# 7segement4digits1badidea-feathershield-m.net
KiCad netlist of a schematic drawn in EAGLE
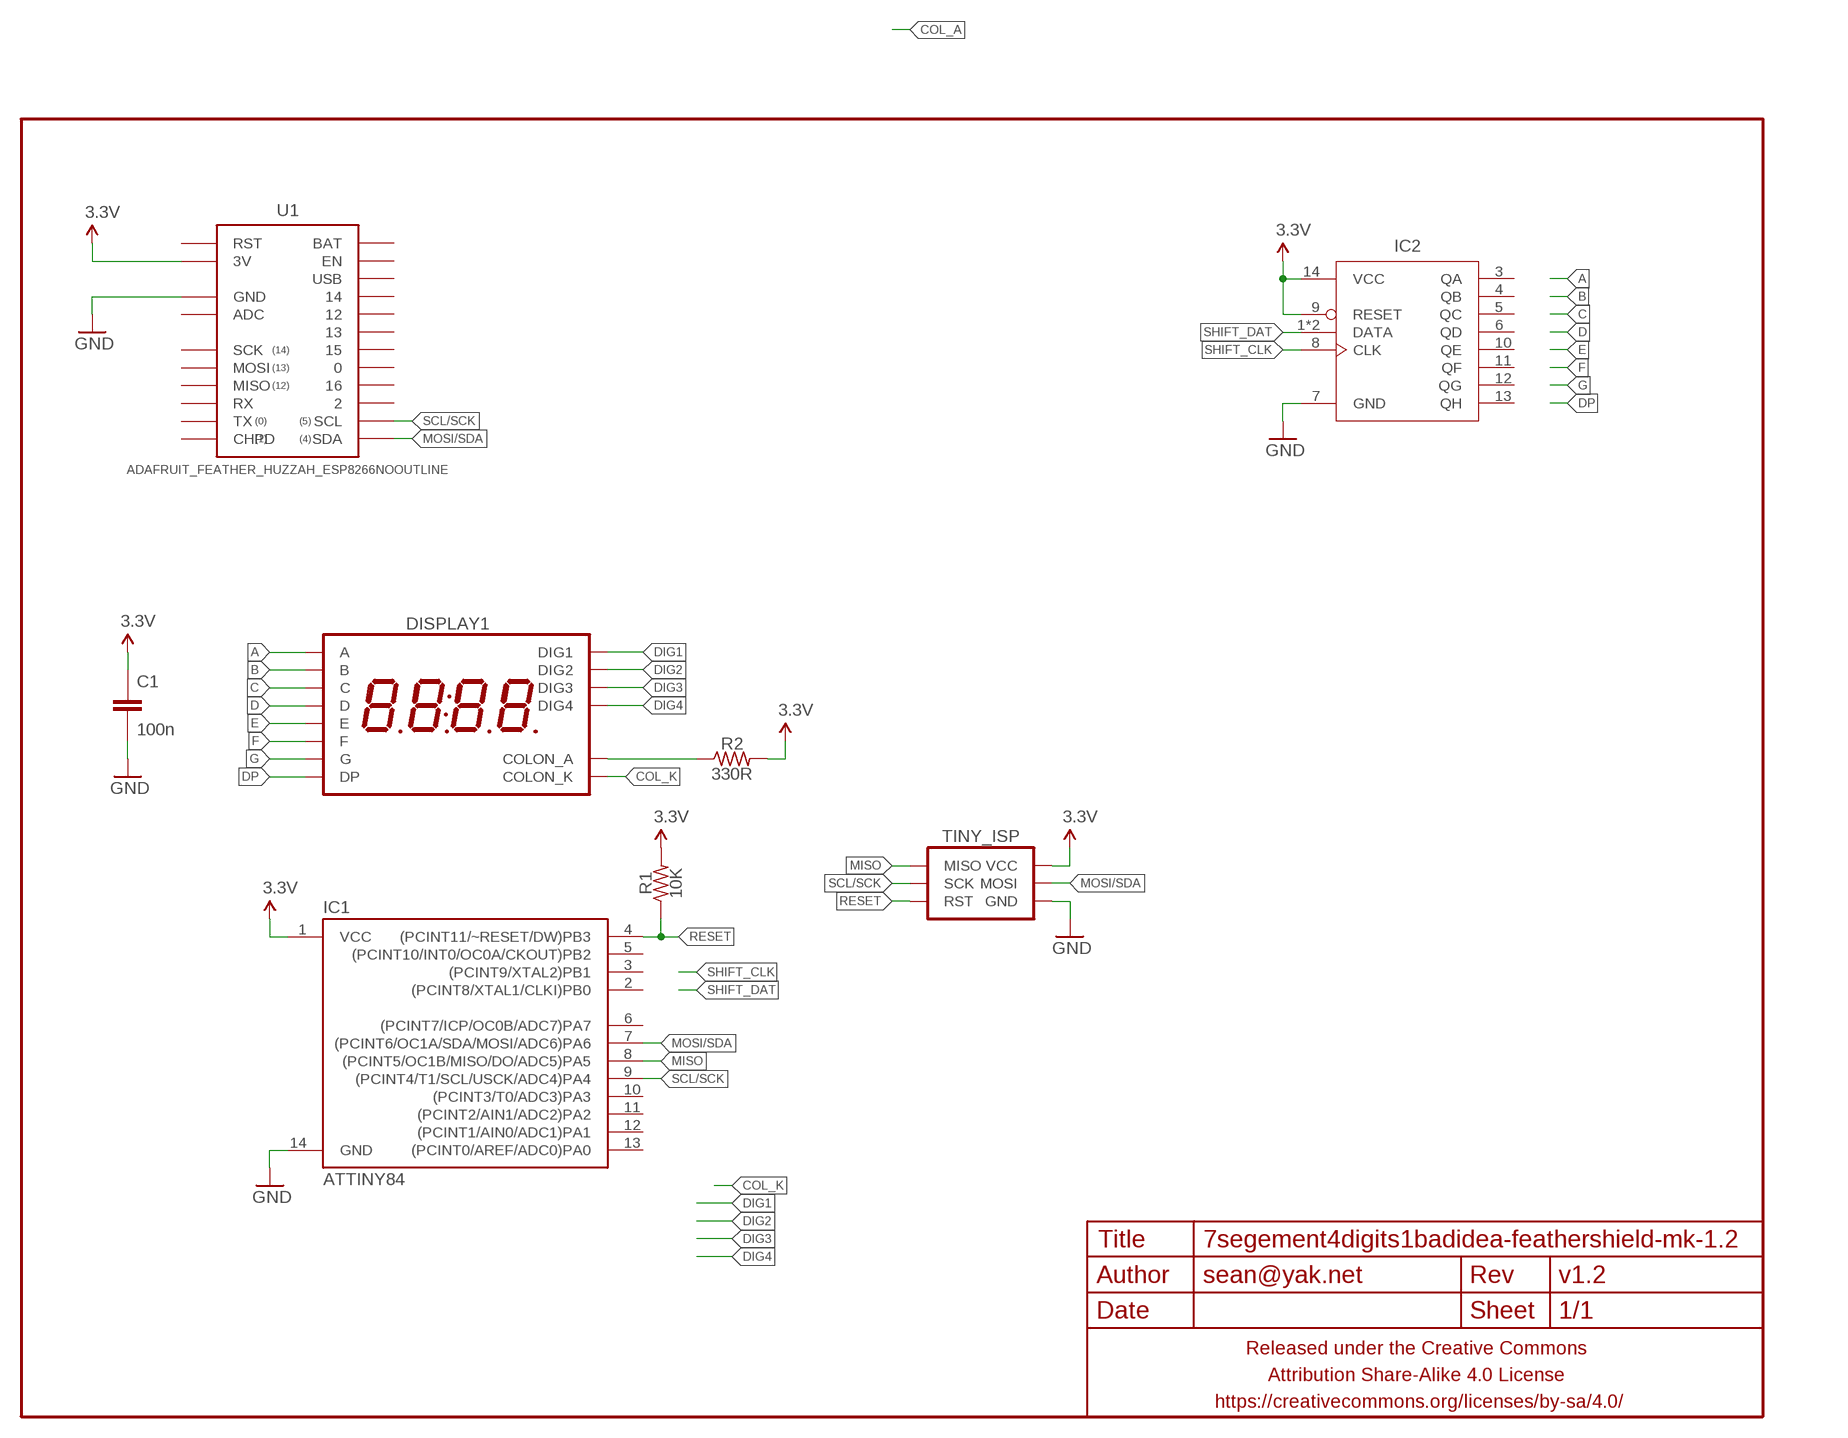
[diagram p0: schematic, sheet 1]

(export (version "E")
  (design (tool "Eeschema 10.0.6"))
  (components
    (comp (ref "C1")
      (value "100n")
      (footprint "eagle-import:C0603")
      (libsource (lib "eagle-import") (part "CAPACITOR-CERAMICC0603"))
    )
    (comp (ref "DISPLAY1")
      (value "7SEG_4DIGIT_COLON14.2MM-CC")
      (footprint "eagle-import:7SEG_4DIG_0.56IN_14MM_ADAFRUIT")
      (libsource (lib "eagle-import") (part "7SEG_4DIGIT_COLON14.2MM-CC"))
    )
    (comp (ref "FRAME1")
      (value "FRAME-LETTERNO_PACKAGE")
      (footprint "eagle-import:DUMMY")
      (fields (field (name "DESIGNER") "sean@yak.net") (field (name "VERSION") "v1.2"))
      (libsource (lib "eagle-import") (part "FRAME-LETTERNO_PACKAGE"))
    )
    (comp (ref "IC1")
      (value "ATTINY84")
      (footprint "eagle-import:SO14")
      (libsource (lib "eagle-import") (part "ATTINY84"))
    )
    (comp (ref "IC2")
      (value "74HC164")
      (footprint "eagle-import:SO14")
      (libsource (lib "eagle-import") (part "74164SOIC"))
    )
    (comp (ref "R1")
      (value "10K")
      (footprint "eagle-import:R0603")
      (libsource (lib "eagle-import") (part "RESISTORR0603"))
    )
    (comp (ref "R2")
      (value "330R")
      (footprint "eagle-import:R0603")
      (libsource (lib "eagle-import") (part "RESISTORR0603"))
    )
    (comp (ref "TINY_ISP")
      (value "AVR_SPI_PRG_6TESTPOINTS")
      (footprint "eagle-import:2X3_TEST_POINTS")
      (libsource (lib "eagle-import") (part "AVR_SPI_PRG_6TESTPOINTS"))
    )
    (comp (ref "U1")
      (value "ADAFRUIT_FEATHER_HUZZAH_ESP8266NOOUTLINE")
      (footprint "eagle-import:ADAFRUIT_FEATHER_HUZZAH_NOOUTLINE")
      (libsource (lib "eagle-import") (part "ADAFRUIT_FEATHER_HUZZAH_ESP8266NOOUTLINE"))
    )
  )
  (nets
    (net (code "1") (name "3.3V") (class "Default")
      (node (ref "C1") (pin "1") (pinfunction "1_1") (pintype "passive"))
      (node (ref "IC1") (pin "1") (pinfunction "VCC_1") (pintype "bidirectional"))
      (node (ref "IC2") (pin "14") (pinfunction "VCC_14") (pintype "bidirectional"))
      (node (ref "IC2") (pin "9") (pinfunction "RESET_9") (pintype "bidirectional"))
      (node (ref "R1") (pin "2") (pinfunction "2_2") (pintype "passive"))
      (node (ref "R2") (pin "2") (pinfunction "2_2") (pintype "passive"))
      (node (ref "TINY_ISP") (pin "2") (pinfunction "VCC_2") (pintype "passive"))
      (node (ref "U1") (pin "3V") (pinfunction "3V_3V") (pintype "bidirectional"))
    )
    (net (code "2") (name "A") (class "Default")
      (node (ref "DISPLAY1") (pin "P$13") (pinfunction "A_P$13") (pintype "passive"))
    )
    (net (code "3") (name "B") (class "Default")
      (node (ref "DISPLAY1") (pin "P$9") (pinfunction "B_P$9") (pintype "passive"))
    )
    (net (code "4") (name "C") (class "Default")
      (node (ref "DISPLAY1") (pin "P$4") (pinfunction "C_P$4") (pintype "passive"))
    )
    (net (code "6") (name "COL_K") (class "Default")
      (node (ref "DISPLAY1") (pin "P$7") (pinfunction "COLON_K_P$7") (pintype "passive"))
    )
    (net (code "7") (name "D") (class "Default")
      (node (ref "DISPLAY1") (pin "P$2") (pinfunction "D_P$2") (pintype "passive"))
    )
    (net (code "8") (name "DIG1") (class "Default")
      (node (ref "DISPLAY1") (pin "P$14") (pinfunction "DIG1_P$14") (pintype "passive"))
    )
    (net (code "9") (name "DIG2") (class "Default")
      (node (ref "DISPLAY1") (pin "P$11") (pinfunction "DIG2_P$11") (pintype "passive"))
    )
    (net (code "10") (name "DIG3") (class "Default")
      (node (ref "DISPLAY1") (pin "P$10") (pinfunction "DIG3_P$10") (pintype "passive"))
    )
    (net (code "11") (name "DIG4") (class "Default")
      (node (ref "DISPLAY1") (pin "P$6") (pinfunction "DIG4_P$6") (pintype "passive"))
    )
    (net (code "12") (name "DP") (class "Default")
      (node (ref "DISPLAY1") (pin "P$3") (pinfunction "DP_P$3") (pintype "passive"))
    )
    (net (code "13") (name "E") (class "Default")
      (node (ref "DISPLAY1") (pin "P$1") (pinfunction "E_P$1") (pintype "passive"))
    )
    (net (code "14") (name "F") (class "Default")
      (node (ref "DISPLAY1") (pin "P$12") (pinfunction "F_P$12") (pintype "passive"))
    )
    (net (code "15") (name "G") (class "Default")
      (node (ref "DISPLAY1") (pin "P$5") (pinfunction "G_P$5") (pintype "passive"))
    )
    (net (code "16") (name "GND") (class "Default")
      (node (ref "C1") (pin "2") (pinfunction "2_2") (pintype "passive"))
      (node (ref "IC1") (pin "14") (pinfunction "GND_14") (pintype "bidirectional"))
      (node (ref "IC2") (pin "7") (pinfunction "GND_7") (pintype "bidirectional"))
      (node (ref "TINY_ISP") (pin "6") (pinfunction "GND_6") (pintype "passive"))
      (node (ref "U1") (pin "GND@0") (pinfunction "GND_GND@0") (pintype "bidirectional"))
    )
    (net (code "17") (name "MISO") (class "Default")
      (node (ref "IC1") (pin "8") (pinfunction "(PCINT5/OC1B/MISO/DO/ADC5)PA5_8") (pintype "bidirectional"))
      (node (ref "TINY_ISP") (pin "1") (pinfunction "MISO_1") (pintype "passive"))
    )
    (net (code "18") (name "MOSI{slash}SDA") (class "Default")
      (node (ref "IC1") (pin "7") (pinfunction "(PCINT6/OC1A/SDA/MOSI/ADC6)PA6_7") (pintype "bidirectional"))
      (node (ref "TINY_ISP") (pin "4") (pinfunction "MOSI_4") (pintype "passive"))
      (node (ref "U1") (pin "SDA") (pinfunction "SDA_SDA") (pintype "bidirectional"))
    )
    (net (code "19") (name "Net-(DISPLAY1-COLON_A)") (class "Default")
      (node (ref "DISPLAY1") (pin "P$8") (pinfunction "COLON_A_P$8") (pintype "passive"))
      (node (ref "R2") (pin "1") (pinfunction "1_1") (pintype "passive"))
    )
    (net (code "20") (name "RESET") (class "Default")
      (node (ref "IC1") (pin "4") (pinfunction "(PCINT11/~{RESET/DW})PB3_4") (pintype "bidirectional"))
      (node (ref "R1") (pin "1") (pinfunction "1_1") (pintype "passive"))
      (node (ref "TINY_ISP") (pin "5") (pinfunction "RST_5") (pintype "passive"))
    )
    (net (code "21") (name "SCL{slash}SCK") (class "Default")
      (node (ref "IC1") (pin "9") (pinfunction "(PCINT4/T1/SCL/USCK/ADC4)PA4_9") (pintype "bidirectional"))
      (node (ref "TINY_ISP") (pin "3") (pinfunction "SCK_3") (pintype "passive"))
      (node (ref "U1") (pin "SCL") (pinfunction "SCL_SCL") (pintype "bidirectional"))
    )
    (net (code "22") (name "SHIFT_CLK") (class "Default")
      (node (ref "IC2") (pin "8") (pinfunction "CLK_8") (pintype "bidirectional"))
    )
    (net (code "23") (name "SHIFT_DAT") (class "Default")
      (node (ref "IC2") (pin "1") (pinfunction "DATA_1") (pintype "bidirectional"))
      (node (ref "IC2") (pin "2") (pinfunction "DATA_2") (pintype "bidirectional"))
    )
    (net (code "24") (name "unconnected-(IC1-(PCINT0{slash}AREF{slash}ADC0)PA0-Pad13)") (class "Default")
      (node (ref "IC1") (pin "13") (pinfunction "(PCINT0/AREF/ADC0)PA0_13") (pintype "bidirectional"))
    )
    (net (code "25") (name "unconnected-(IC1-(PCINT1{slash}AIN0{slash}ADC1)PA1-Pad12)") (class "Default")
      (node (ref "IC1") (pin "12") (pinfunction "(PCINT1/AIN0/ADC1)PA1_12") (pintype "bidirectional"))
    )
    (net (code "26") (name "unconnected-(IC1-(PCINT2{slash}AIN1{slash}ADC2)PA2-Pad11)") (class "Default")
      (node (ref "IC1") (pin "11") (pinfunction "(PCINT2/AIN1/ADC2)PA2_11") (pintype "bidirectional"))
    )
    (net (code "27") (name "unconnected-(IC1-(PCINT3{slash}T0{slash}ADC3)PA3-Pad10)") (class "Default")
      (node (ref "IC1") (pin "10") (pinfunction "(PCINT3/T0/ADC3)PA3_10") (pintype "bidirectional"))
    )
    (net (code "28") (name "unconnected-(IC1-(PCINT7{slash}ICP{slash}OC0B{slash}ADC7)PA7-Pad6)") (class "Default")
      (node (ref "IC1") (pin "6") (pinfunction "(PCINT7/ICP/OC0B/ADC7)PA7_6") (pintype "bidirectional"))
    )
    (net (code "29") (name "unconnected-(IC1-(PCINT8{slash}XTAL1{slash}CLKI)PB0-Pad2)") (class "Default")
      (node (ref "IC1") (pin "2") (pinfunction "(PCINT8/XTAL1/CLKI)PB0_2") (pintype "bidirectional"))
    )
    (net (code "30") (name "unconnected-(IC1-(PCINT9{slash}XTAL2)PB1-Pad3)") (class "Default")
      (node (ref "IC1") (pin "3") (pinfunction "(PCINT9/XTAL2)PB1_3") (pintype "bidirectional"))
    )
    (net (code "31") (name "unconnected-(IC1-(PCINT10{slash}INT0{slash}OC0A{slash}CKOUT)PB2-Pad5)") (class "Default")
      (node (ref "IC1") (pin "5") (pinfunction "(PCINT10/INT0/OC0A/CKOUT)PB2_5") (pintype "bidirectional"))
    )
    (net (code "32") (name "unconnected-(IC2-QA-Pad3)") (class "Default")
      (node (ref "IC2") (pin "3") (pinfunction "QA_3") (pintype "bidirectional"))
    )
    (net (code "33") (name "unconnected-(IC2-QB-Pad4)") (class "Default")
      (node (ref "IC2") (pin "4") (pinfunction "QB_4") (pintype "bidirectional"))
    )
    (net (code "34") (name "unconnected-(IC2-QC-Pad5)") (class "Default")
      (node (ref "IC2") (pin "5") (pinfunction "QC_5") (pintype "bidirectional"))
    )
    (net (code "35") (name "unconnected-(IC2-QD-Pad6)") (class "Default")
      (node (ref "IC2") (pin "6") (pinfunction "QD_6") (pintype "bidirectional"))
    )
    (net (code "36") (name "unconnected-(IC2-QE-Pad10)") (class "Default")
      (node (ref "IC2") (pin "10") (pinfunction "QE_10") (pintype "bidirectional"))
    )
    (net (code "37") (name "unconnected-(IC2-QF-Pad11)") (class "Default")
      (node (ref "IC2") (pin "11") (pinfunction "QF_11") (pintype "bidirectional"))
    )
    (net (code "38") (name "unconnected-(IC2-QG-Pad12)") (class "Default")
      (node (ref "IC2") (pin "12") (pinfunction "QG_12") (pintype "bidirectional"))
    )
    (net (code "39") (name "unconnected-(IC2-QH-Pad13)") (class "Default")
      (node (ref "IC2") (pin "13") (pinfunction "QH_13") (pintype "bidirectional"))
    )
    (net (code "40") (name "unconnected-(U1-Pad0)") (class "Default")
      (node (ref "U1") (pin "0") (pinfunction "0_0") (pintype "bidirectional"))
    )
    (net (code "41") (name "unconnected-(U1-Pad2)") (class "Default")
      (node (ref "U1") (pin "2") (pinfunction "2_2") (pintype "bidirectional"))
    )
    (net (code "42") (name "unconnected-(U1-Pad12)") (class "Default")
      (node (ref "U1") (pin "12") (pinfunction "12_12") (pintype "bidirectional"))
    )
    (net (code "43") (name "unconnected-(U1-Pad13)") (class "Default")
      (node (ref "U1") (pin "13") (pinfunction "13_13") (pintype "bidirectional"))
    )
    (net (code "44") (name "unconnected-(U1-Pad14)") (class "Default")
      (node (ref "U1") (pin "14") (pinfunction "14_14") (pintype "bidirectional"))
    )
    (net (code "45") (name "unconnected-(U1-Pad15)") (class "Default")
      (node (ref "U1") (pin "15") (pinfunction "15_15") (pintype "bidirectional"))
    )
    (net (code "46") (name "unconnected-(U1-Pad16)") (class "Default")
      (node (ref "U1") (pin "16") (pinfunction "16_16") (pintype "bidirectional"))
    )
    (net (code "47") (name "unconnected-(U1-PadADC)") (class "Default")
      (node (ref "U1") (pin "ADC") (pinfunction "ADC_ADC") (pintype "bidirectional"))
    )
    (net (code "48") (name "unconnected-(U1-PadBAT)") (class "Default")
      (node (ref "U1") (pin "BAT") (pinfunction "BAT_BAT") (pintype "bidirectional"))
    )
    (net (code "49") (name "unconnected-(U1-PadCHPD)") (class "Default")
      (node (ref "U1") (pin "CHPD") (pinfunction "CHPD_CHPD") (pintype "bidirectional"))
    )
    (net (code "50") (name "unconnected-(U1-PadEN)") (class "Default")
      (node (ref "U1") (pin "EN") (pinfunction "EN_EN") (pintype "bidirectional"))
    )
    (net (code "51") (name "unconnected-(U1-PadMISO)") (class "Default")
      (node (ref "U1") (pin "MISO") (pinfunction "MISO_MISO") (pintype "bidirectional"))
    )
    (net (code "52") (name "unconnected-(U1-PadMOSI)") (class "Default")
      (node (ref "U1") (pin "MOSI") (pinfunction "MOSI_MOSI") (pintype "bidirectional"))
    )
    (net (code "53") (name "unconnected-(U1-PadRST)") (class "Default")
      (node (ref "U1") (pin "RST") (pinfunction "RST_RST") (pintype "bidirectional"))
    )
    (net (code "54") (name "unconnected-(U1-PadRX)") (class "Default")
      (node (ref "U1") (pin "RX") (pinfunction "RX_RX") (pintype "bidirectional"))
    )
    (net (code "55") (name "unconnected-(U1-PadSCK)") (class "Default")
      (node (ref "U1") (pin "SCK") (pinfunction "SCK_SCK") (pintype "bidirectional"))
    )
    (net (code "56") (name "unconnected-(U1-PadTX)") (class "Default")
      (node (ref "U1") (pin "TX") (pinfunction "TX_TX") (pintype "bidirectional"))
    )
    (net (code "57") (name "unconnected-(U1-PadUSB)") (class "Default")
      (node (ref "U1") (pin "USB") (pinfunction "USB_USB") (pintype "bidirectional"))
    )
  )
)
